# Ada_-_Sensor_-_daugher_board_4_0.net
KiCad netlist of a schematic drawn in Altium Designer
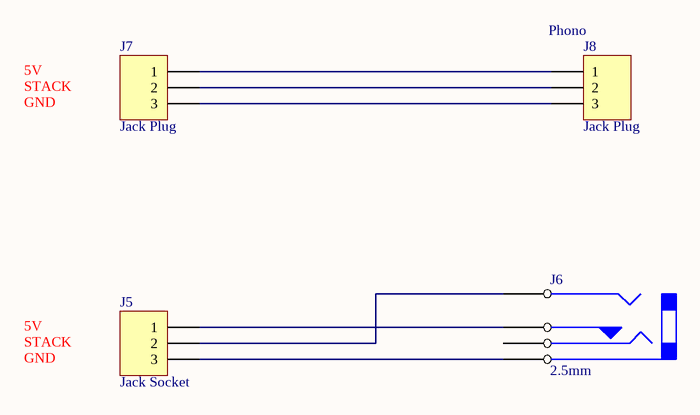
[diagram p0: Ada - Sensor - daugher board 4.0.SchDoc]

(export (version "E")
  (design (tool "Eeschema 10.0.6"))
  (components
    (comp (ref "J5")
      (value "Jack Socket")
      (footprint "SIP3")
      (description "Header, 3-Pin")
      (libsource (lib "Miscellaneous Connectors") (part "Header 3"))
    )
    (comp (ref "J6")
      (value "2.5mm")
      (footprint "TRI002_Baseblock_issue 1.1:2.5mm socket TRI001")
      (description "2.5mm PHONEJACK STEREO")
      (fields (field (name "MANUFACTURER") "PRO SIGNAL") (field (name "MANUF PART #") "PSG01539"))
      (libsource (lib "TRI001") (part "2.5mm PHONEJACK STEREO TRI001"))
    )
    (comp (ref "J7")
      (value "Jack Plug")
      (footprint "sip3")
      (description "Header, 3-Pin")
      (libsource (lib "Miscellaneous Connectors") (part "Header 3"))
    )
    (comp (ref "J8")
      (value "Jack Plug")
      (footprint "DC_JACK_PCB_MOUNT")
      (description "Header, 3-Pin")
      (fields
        (field (name "MANUFACTURER") "BKL")
        (field (name "MANUF PART #") "1107002  EAN-13: 2050000222993")
        (field (name "ALTIUM_VALUE") "Phono")
      )
      (libsource (lib "") (part "Header 3_1"))
    )
  )
  (nets
    (net (code "1") (name "Net-(J5-Pad1)") (class "Default")
      (node (ref "J5") (pin "1") (pinfunction "1_1") (pintype "passive"))
      (node (ref "J6") (pin "2") (pinfunction "2_2") (pintype "passive"))
    )
    (net (code "2") (name "Net-(J5-Pad2)") (class "Default")
      (node (ref "J5") (pin "2") (pinfunction "2_2") (pintype "passive"))
      (node (ref "J6") (pin "4") (pinfunction "4_4") (pintype "passive"))
    )
    (net (code "3") (name "Net-(J5-Pad3)") (class "Default")
      (node (ref "J5") (pin "3") (pinfunction "3_3") (pintype "passive"))
      (node (ref "J6") (pin "1") (pinfunction "1_1") (pintype "passive"))
    )
    (net (code "4") (name "Net-(J7-Pad1)") (class "Default")
      (node (ref "J7") (pin "1") (pinfunction "1_1") (pintype "passive"))
      (node (ref "J8") (pin "1") (pinfunction "1_1") (pintype "passive"))
    )
    (net (code "5") (name "Net-(J7-Pad2)") (class "Default")
      (node (ref "J7") (pin "2") (pinfunction "2_2") (pintype "passive"))
      (node (ref "J8") (pin "2") (pinfunction "2_2") (pintype "passive"))
    )
    (net (code "6") (name "Net-(J7-Pad3)") (class "Default")
      (node (ref "J7") (pin "3") (pinfunction "3_3") (pintype "passive"))
      (node (ref "J8") (pin "3") (pinfunction "3_3") (pintype "passive"))
    )
    (net (code "7") (name "unconnected-(J6-Pad3)") (class "Default")
      (node (ref "J6") (pin "3") (pinfunction "3_3") (pintype "passive"))
    )
  )
)
